# InputPort.net
KiCad netlist of a schematic drawn in Altium Designer
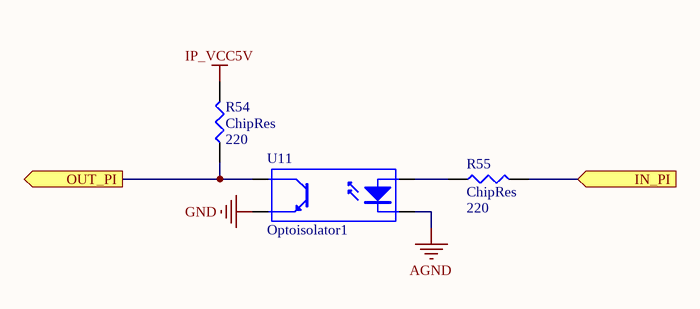
[diagram p0: InputPort.SchDoc]

(export (version "E")
  (design (tool "Eeschema 10.0.6"))
  (components
    (comp (ref "R54")
      (value "ChipRes")
      (footprint "RES0805")
      (description "Chip resistor")
      (fields (field (name "ALTIUM_VALUE") "220"))
      (libsource (lib "Common Devices") (part "ChipRes"))
    )
    (comp (ref "R55")
      (value "ChipRes")
      (footprint "RES0805")
      (description "Chip resistor")
      (fields (field (name "ALTIUM_VALUE") "220"))
      (libsource (lib "Common Devices") (part "ChipRes"))
    )
    (comp (ref "U11")
      (value "Optoisolator1")
      (footprint "DIP-4")
      (description "4-Pin Phototransistor Optocoupler")
      (fields (field (name "PUBLISHER") "Altium Limited"))
      (libsource (lib "Miscellaneous Devices") (part "Optoisolator1"))
    )
  )
  (nets
    (net (code "1") (name "/IN_PI") (class "Default") (node (ref "R55") (pin "2") (pintype "passive")))
    (net (code "2") (name "/OUT_PI") (class "Default")
      (node (ref "R54") (pin "1") (pintype "passive"))
      (node (ref "U11") (pin "4") (pinfunction "C_4") (pintype "passive"))
    )
    (net (code "3") (name "AGND") (class "Default")
      (node (ref "U11") (pin "2") (pinfunction "K_2") (pintype "passive"))
    )
    (net (code "4") (name "GND") (class "Default")
      (node (ref "U11") (pin "3") (pinfunction "E_3") (pintype "passive"))
    )
    (net (code "5") (name "IP_VCC5V") (class "Default") (node (ref "R54") (pin "2") (pintype "passive")))
    (net (code "6") (name "Net-(U11-A)") (class "Default")
      (node (ref "R55") (pin "1") (pintype "passive"))
      (node (ref "U11") (pin "1") (pinfunction "A_1") (pintype "passive"))
    )
  )
)
